# Voeding.net
KiCad netlist of a schematic drawn in Altium Designer
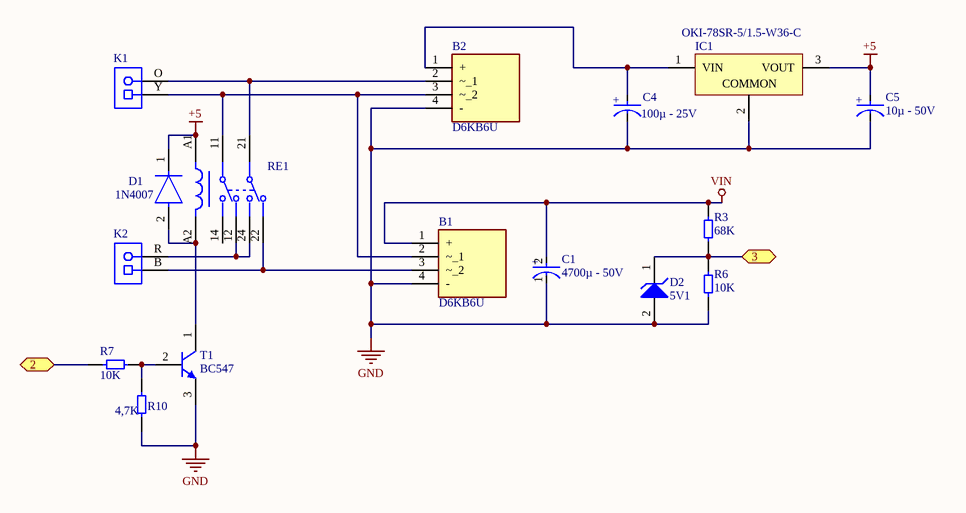
[diagram p0: Voeding.SchDoc]

(export (version "E")
  (design (tool "Eeschema 10.0.6"))
  (components
    (comp (ref "B1")
      (value "D6KB6U")
      (footprint "GSIB1580E345")
      (description "Bridge Rectifier Diode 15A 800V GSIB-5S")
      (fields
        (field (name "MOUSER PART NUMBER") "625-GSIB1580-E3")
        (field (name "MANUFACTURER_PART_NUMBER") "GSIB1580-E3/45")
      )
      (libsource (lib "Soldeerstation") (part "GSIB1580-E3_45"))
    )
    (comp (ref "B2")
      (value "D6KB6U")
      (footprint "GSIB1580E345")
      (description "Bridge Rectifier Diode 15A 800V GSIB-5S")
      (fields
        (field (name "MOUSER PART NUMBER") "625-GSIB1580-E3")
        (field (name "MANUFACTURER_PART_NUMBER") "GSIB1580-E3/45")
      )
      (libsource (lib "Soldeerstation") (part "GSIB1580-E3_45"))
    )
    (comp (ref "C1")
      (value "4700µ - 50V")
      (footprint "U1-UU_NCH")
      (description "Aluminum Electrolytic Capacitors (Radial Lead Type) 100uF ±20% 25V")
      (fields (field (name "TOLERANCE") "20%"))
      (libsource (lib "Soldeerstation") (part "CMP-05427-000897-1"))
    )
    (comp (ref "C4")
      (value "100µ - 25V")
      (footprint "FP-RAD-TH-D_6_3_0_5-L_11-MFG")
      (description "Aluminum Electrolytic Capacitors (Radial Lead Type) 100uF ±20% 25V")
      (fields (field (name "TOLERANCE") "20%"))
      (libsource (lib "") (part "CMP-05427-000897-1_1"))
    )
    (comp (ref "C5")
      (value "10µ - 50V")
      (footprint "CAPPRD200W52D525H1200")
      (description "Aluminum Electrolytic Capacitors (Radial Lead Type) 100uF ±20% 25V")
      (fields (field (name "TOLERANCE") "20%"))
      (libsource (lib "") (part "CMP-05427-000897-1_1"))
    )
    (comp (ref "D1")
      (value "1N4007")
      (footprint "FP-1N4007-MFG")
      (description "Rectifier diode 1000 V 1 A DO-41, ,")
      (fields
        (field (name "MANUFACTURER") "Diotec")
        (field (name "OCTOPART") "https://octopart.com/1n4007-diotec-4040411")
      )
      (libsource (lib "Soldeerstation") (part "CMP-123542-000001-1"))
    )
    (comp (ref "D2")
      (value "5V1")
      (footprint "FP-IR02-MFG")
      (description "Zener Voltage Regulator, 500 mW, 2-Pin SOD-123, Pb-Free, Tape and Reel")
      (fields (field (name "MANUFACTURER") "On Semiconductor") (field (name "PARTNUMBER") "MMSZ4689ET1G"))
      (libsource (lib "Soldeerstation") (part "CMP-1060-00390-1"))
    )
    (comp (ref "IC1")
      (value "OKI-78SR-5/1.5-W36-C")
      (footprint "MURA-OKI-78SR-3")
      (description "Non-Isolated DC/DC Converter, 7.5 W, 7 to 36 V, 1.5 A, -40 to 85 degC, 3-Pin THD, RoHS")
      (fields (field (name "MANUFACTURER") "Murata"))
      (libsource (lib "Soldeerstation") (part "CMP-2000-05274-1"))
    )
    (comp (ref "K1")
      (value "1729128")
      (footprint "PHOE-1729128-2_V")
      (description "PCB Terminal Block, 13.5 A, 400 V, 2-Pin THD, RoHS, Bulk")
      (fields (field (name "MANUFACTURER") "Phoenix Contact"))
      (libsource (lib "") (part "CMP-2000-05815-1_1"))
    )
    (comp (ref "K2")
      (value "1729128")
      (footprint "PHOE-1729128-2_V")
      (description "PCB Terminal Block, 13.5 A, 400 V, 2-Pin THD, RoHS, Bulk")
      (fields (field (name "MANUFACTURER") "Phoenix Contact"))
      (libsource (lib "Soldeerstation") (part "CMP-2000-05815-1"))
    )
    (comp (ref "R3")
      (value "68K")
      (footprint "RESC2013X60X40ML20T25")
      (fields (field (name "PART NUMBER") "ERA6AEB332V") (field (name "MANUFACTURER") "Panasonic"))
      (libsource (lib "Soldeerstation") (part "CMP-2001-00629-1_1"))
    )
    (comp (ref "R6")
      (value "10K")
      (footprint "RESC2013X60X40ML20T25")
      (fields (field (name "PART NUMBER") "ERA6AEB332V") (field (name "MANUFACTURER") "Panasonic"))
      (libsource (lib "Soldeerstation") (part "CMP-2001-00629-1_1"))
    )
    (comp (ref "R7")
      (value "10K")
      (footprint "RESC2013X60X40ML20T25")
      (fields (field (name "PART NUMBER") "ERA6AEB332V") (field (name "MANUFACTURER") "Panasonic"))
      (libsource (lib "Soldeerstation") (part "CMP-2001-00629-1_1"))
    )
    (comp (ref "R10")
      (value "4,7K")
      (footprint "RESC2013X60X40ML20T25")
      (fields (field (name "PART NUMBER") "ERA6AEB332V") (field (name "MANUFACTURER") "Panasonic"))
      (libsource (lib "Soldeerstation") (part "CMP-2001-00629-1_1"))
    )
    (comp (ref "RE1")
      (value "RT424005F")
      (footprint "FP-RT424005F-MFG")
      (description "RELAY GENERAL PURPOSE DPDT 8A 5V")
      (libsource (lib "Soldeerstation") (part "CMP-03395-000296-1"))
    )
    (comp (ref "T1")
      (value "BC547")
      (footprint "ONSC-TO-92-3-29-11")
      (description "Amplifier Transistor, NPN Silicon, 3-Pin TO-92, Pb-Free, Bulk Box")
      (fields (field (name "MANUFACTURER") "On Semiconductor") (field (name "PARTNUMBER") "BC547CG"))
      (libsource (lib "Soldeerstation") (part "CMP-1048-01464-1"))
    )
  )
  (nets
    (net (code "1") (name "+5") (class "Default")
      (node (ref "C5") (pin "2") (pinfunction "A_2") (pintype "passive"))
      (node (ref "D1") (pin "1") (pinfunction "C_1") (pintype "passive"))
      (node (ref "IC1") (pin "3") (pinfunction "VOUT_3") (pintype "power_in"))
      (node (ref "RE1") (pin "A1") (pinfunction "A1_A1") (pintype "passive"))
    )
    (net (code "2") (name "/2") (class "Default")
      (node (ref "R7") (pin "1") (pinfunction "1_1") (pintype "passive"))
    )
    (net (code "3") (name "/3") (class "Default")
      (node (ref "D2") (pin "1") (pinfunction "K_1") (pintype "passive"))
      (node (ref "R3") (pin "1") (pinfunction "1_1") (pintype "passive"))
      (node (ref "R6") (pin "1") (pinfunction "1_1") (pintype "passive"))
    )
    (net (code "4") (name "GND") (class "Default")
      (node (ref "B1") (pin "4") (pinfunction "-_4") (pintype "passive"))
      (node (ref "B2") (pin "4") (pinfunction "-_4") (pintype "passive"))
      (node (ref "C1") (pin "1") (pinfunction "C_1") (pintype "passive"))
      (node (ref "C4") (pin "1") (pinfunction "C_1") (pintype "passive"))
      (node (ref "C5") (pin "1") (pinfunction "C_1") (pintype "passive"))
      (node (ref "D2") (pin "2") (pinfunction "A_2") (pintype "passive"))
      (node (ref "IC1") (pin "2") (pinfunction "COMMON_2") (pintype "power_in"))
      (node (ref "R10") (pin "1") (pinfunction "1_1") (pintype "passive"))
      (node (ref "R6") (pin "2") (pinfunction "2_2") (pintype "passive"))
      (node (ref "T1") (pin "3") (pinfunction "E_3") (pintype "passive"))
    )
    (net (code "5") (name "Net-(B1-~_1)") (class "Default")
      (node (ref "B1") (pin "2") (pinfunction "~_1_2") (pintype "passive"))
      (node (ref "B2") (pin "3") (pinfunction "~_2_3") (pintype "passive"))
      (node (ref "K1") (pin "Y") (pinfunction "1_Y") (pintype "passive"))
      (node (ref "RE1") (pin "11") (pinfunction "11_11") (pintype "passive"))
    )
    (net (code "6") (name "Net-(B1-~_2)") (class "Default")
      (node (ref "B1") (pin "3") (pinfunction "~_2_3") (pintype "passive"))
      (node (ref "K2") (pin "B") (pinfunction "1_B") (pintype "passive"))
      (node (ref "RE1") (pin "22") (pinfunction "22_22") (pintype "passive"))
    )
    (net (code "7") (name "Net-(B2-+)") (class "Default")
      (node (ref "B2") (pin "1") (pinfunction "+_1") (pintype "passive"))
      (node (ref "C4") (pin "2") (pinfunction "A_2") (pintype "passive"))
      (node (ref "IC1") (pin "1") (pinfunction "VIN_1") (pintype "power_in"))
    )
    (net (code "8") (name "Net-(B2-~_1)") (class "Default")
      (node (ref "B2") (pin "2") (pinfunction "~_1_2") (pintype "passive"))
      (node (ref "K1") (pin "O") (pinfunction "2_O") (pintype "passive"))
      (node (ref "RE1") (pin "21") (pinfunction "21_21") (pintype "passive"))
    )
    (net (code "9") (name "Net-(D1-A)") (class "Default")
      (node (ref "D1") (pin "2") (pinfunction "A_2") (pintype "passive"))
      (node (ref "RE1") (pin "A2") (pinfunction "A2_A2") (pintype "passive"))
      (node (ref "T1") (pin "1") (pinfunction "C_1") (pintype "passive"))
    )
    (net (code "10") (name "Net-(K2-2)") (class "Default")
      (node (ref "K2") (pin "R") (pinfunction "2_R") (pintype "passive"))
      (node (ref "RE1") (pin "12") (pinfunction "12_12") (pintype "passive"))
      (node (ref "RE1") (pin "24") (pinfunction "24_24") (pintype "passive"))
    )
    (net (code "11") (name "Net-(T1-B)") (class "Default")
      (node (ref "R10") (pin "2") (pinfunction "2_2") (pintype "passive"))
      (node (ref "R7") (pin "2") (pinfunction "2_2") (pintype "passive"))
      (node (ref "T1") (pin "2") (pinfunction "B_2") (pintype "passive"))
    )
    (net (code "12") (name "VIN") (class "Default")
      (node (ref "B1") (pin "1") (pinfunction "+_1") (pintype "passive"))
      (node (ref "C1") (pin "2") (pinfunction "A_2") (pintype "passive"))
      (node (ref "R3") (pin "2") (pinfunction "2_2") (pintype "passive"))
    )
    (net (code "13") (name "unconnected-(RE1-Pad14)") (class "Default")
      (node (ref "RE1") (pin "14") (pinfunction "14_14") (pintype "passive"))
    )
  )
)
